# MB1256.net
KiCad netlist of a schematic drawn in Altium Designer
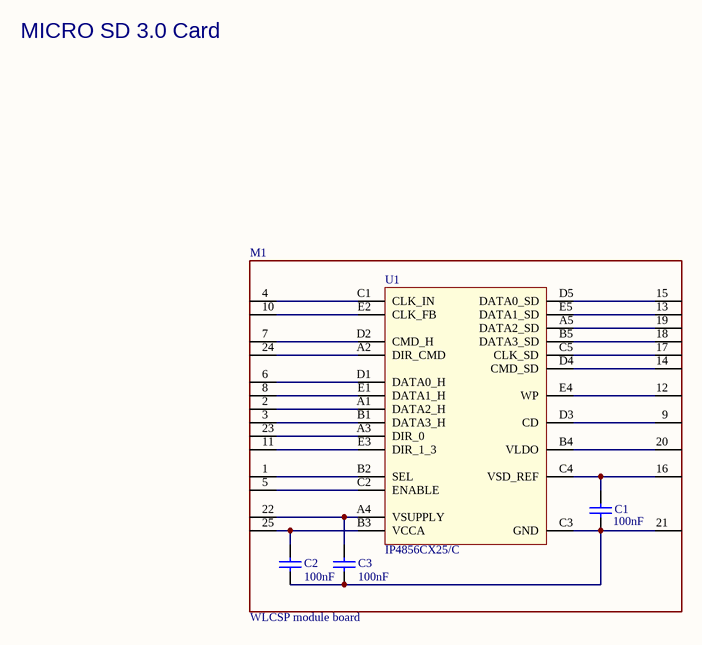
[diagram p0: MB1256.SchDoc]

(export (version "E")
  (design (tool "Eeschema 10.0.6"))
  (components
    (comp (ref "C1")
      (value "100nF")
      (footprint "0402C")
      (description "Capacitor")
      (fields (field (name "PUBLISHER") "Altium Limited"))
      (libsource (lib "Miscellaneous Devices") (part "Cap"))
    )
    (comp (ref "C2")
      (value "100nF")
      (footprint "0402C")
      (description "Capacitor")
      (fields (field (name "PUBLISHER") "Altium Limited"))
      (libsource (lib "Miscellaneous Devices") (part "Cap"))
    )
    (comp (ref "C3")
      (value "100nF")
      (footprint "0402C")
      (description "Capacitor")
      (fields (field (name "PUBLISHER") "Altium Limited"))
      (libsource (lib "Miscellaneous Devices") (part "Cap"))
    )
    (comp (ref "M1")
      (value "WLCSP module board")
      (footprint "WLCSP25_0R4_2R05X2R05_module")
      (libsource (lib "SD module board") (part "WLCSP module board"))
    )
    (comp (ref "U1")
      (value "IP4856CX25/C")
      (footprint "WLCSP25_0R4_2R05X2R05")
      (description "SDcard3.0 dual voltage level  translator")
      (libsource (lib "MB1246") (part "IP4856CX25/C"))
    )
  )
  (nets
    (net (code "1") (name "Net-(M1-CD)") (class "Default")
      (node (ref "C3") (pin "1") (pinfunction "1_1") (pintype "passive"))
      (node (ref "M1") (pin "22") (pinfunction "CD_22") (pintype "passive"))
      (node (ref "U1") (pin "A4") (pinfunction "VSUPPLY_A4") (pintype "passive"))
    )
    (net (code "2") (name "Net-(M1-CLK_FB)") (class "Default")
      (node (ref "M1") (pin "2") (pinfunction "CLK_FB_2") (pintype "passive"))
      (node (ref "U1") (pin "A1") (pinfunction "DATA2_H_A1") (pintype "passive"))
    )
    (net (code "3") (name "Net-(M1-CLK_IN)") (class "Default")
      (node (ref "M1") (pin "1") (pinfunction "CLK_IN_1") (pintype "passive"))
      (node (ref "U1") (pin "B2") (pinfunction "SEL_B2") (pintype "passive"))
    )
    (net (code "4") (name "Net-(M1-CLK_SD)") (class "Default")
      (node (ref "M1") (pin "19") (pinfunction "CLK_SD_19") (pintype "passive"))
      (node (ref "U1") (pin "A5") (pinfunction "DATA2_SD_A5") (pintype "passive"))
    )
    (net (code "5") (name "Net-(M1-CMD_H)") (class "Default")
      (node (ref "M1") (pin "3") (pinfunction "CMD_H_3") (pintype "passive"))
      (node (ref "U1") (pin "B1") (pinfunction "DATA3_H_B1") (pintype "passive"))
    )
    (net (code "6") (name "Net-(M1-CMD_SD)") (class "Default")
      (node (ref "M1") (pin "20") (pinfunction "CMD_SD_20") (pintype "passive"))
      (node (ref "U1") (pin "B4") (pinfunction "VLDO_B4") (pintype "passive"))
    )
    (net (code "7") (name "Net-(M1-DATA0_H)") (class "Default")
      (node (ref "M1") (pin "5") (pinfunction "DATA0_H_5") (pintype "passive"))
      (node (ref "U1") (pin "C2") (pinfunction "ENABLE_C2") (pintype "passive"))
    )
    (net (code "8") (name "Net-(M1-DATA0_SD)") (class "Default")
      (node (ref "M1") (pin "15") (pinfunction "DATA0_SD_15") (pintype "passive"))
      (node (ref "U1") (pin "D5") (pinfunction "DATA0_SD_D5") (pintype "passive"))
    )
    (net (code "9") (name "Net-(M1-DATA1_H)") (class "Default")
      (node (ref "M1") (pin "6") (pinfunction "DATA1_H_6") (pintype "passive"))
      (node (ref "U1") (pin "D1") (pinfunction "DATA0_H_D1") (pintype "passive"))
    )
    (net (code "10") (name "Net-(M1-DATA1_SD)") (class "Default")
      (node (ref "C1") (pin "1") (pinfunction "1_1") (pintype "passive"))
      (node (ref "M1") (pin "16") (pinfunction "DATA1_SD_16") (pintype "passive"))
      (node (ref "U1") (pin "C4") (pinfunction "VSD_REF_C4") (pintype "passive"))
    )
    (net (code "11") (name "Net-(M1-DATA2_H)") (class "Default")
      (node (ref "M1") (pin "7") (pinfunction "DATA2_H_7") (pintype "passive"))
      (node (ref "U1") (pin "D2") (pinfunction "CMD_H_D2") (pintype "passive"))
    )
    (net (code "12") (name "Net-(M1-DATA2_SD)") (class "Default")
      (node (ref "M1") (pin "17") (pinfunction "DATA2_SD_17") (pintype "passive"))
      (node (ref "U1") (pin "C5") (pinfunction "CLK_SD_C5") (pintype "passive"))
    )
    (net (code "13") (name "Net-(M1-DATA3_H)") (class "Default")
      (node (ref "M1") (pin "8") (pinfunction "DATA3_H_8") (pintype "passive"))
      (node (ref "U1") (pin "E1") (pinfunction "DATA1_H_E1") (pintype "passive"))
    )
    (net (code "14") (name "Net-(M1-DATA3_SD)") (class "Default")
      (node (ref "M1") (pin "18") (pinfunction "DATA3_SD_18") (pintype "passive"))
      (node (ref "U1") (pin "B5") (pinfunction "DATA3_SD_B5") (pintype "passive"))
    )
    (net (code "15") (name "Net-(M1-DIR_0)") (class "Default")
      (node (ref "M1") (pin "9") (pinfunction "DIR_0_9") (pintype "passive"))
      (node (ref "U1") (pin "D3") (pinfunction "CD_D3") (pintype "passive"))
    )
    (net (code "16") (name "Net-(M1-DIR_1_3)") (class "Default")
      (node (ref "M1") (pin "10") (pinfunction "DIR_1_3_10") (pintype "passive"))
      (node (ref "U1") (pin "E2") (pinfunction "CLK_FB_E2") (pintype "passive"))
    )
    (net (code "17") (name "Net-(M1-DIR_CMD)") (class "Default")
      (node (ref "M1") (pin "4") (pinfunction "DIR_CMD_4") (pintype "passive"))
      (node (ref "U1") (pin "C1") (pinfunction "CLK_IN_C1") (pintype "passive"))
    )
    (net (code "18") (name "Net-(M1-ENABLE)") (class "Default")
      (node (ref "M1") (pin "12") (pinfunction "ENABLE_12") (pintype "passive"))
      (node (ref "U1") (pin "E4") (pinfunction "WP_E4") (pintype "passive"))
    )
    (net (code "19") (name "Net-(M1-GND)") (class "Default")
      (node (ref "C2") (pin "1") (pinfunction "1_1") (pintype "passive"))
      (node (ref "M1") (pin "25") (pinfunction "GND_25") (pintype "passive"))
      (node (ref "U1") (pin "B3") (pinfunction "VCCA_B3") (pintype "passive"))
    )
    (net (code "20") (name "Net-(M1-SEL)") (class "Default")
      (node (ref "M1") (pin "11") (pinfunction "SEL_11") (pintype "passive"))
      (node (ref "U1") (pin "E3") (pinfunction "DIR_1_3_E3") (pintype "passive"))
    )
    (net (code "21") (name "Net-(M1-VCCA)") (class "Default")
      (node (ref "M1") (pin "14") (pinfunction "VCCA_14") (pintype "passive"))
      (node (ref "U1") (pin "D4") (pinfunction "CMD_SD_D4") (pintype "passive"))
    )
    (net (code "22") (name "Net-(M1-VLDO)") (class "Default")
      (node (ref "M1") (pin "23") (pinfunction "VLDO_23") (pintype "passive"))
      (node (ref "U1") (pin "A3") (pinfunction "DIR_0_A3") (pintype "passive"))
    )
    (net (code "23") (name "Net-(M1-VSD_REF)") (class "Default")
      (node (ref "M1") (pin "24") (pinfunction "VSD_REF_24") (pintype "passive"))
      (node (ref "U1") (pin "A2") (pinfunction "DIR_CMD_A2") (pintype "passive"))
    )
    (net (code "24") (name "Net-(M1-VSUPPLY)") (class "Default")
      (node (ref "M1") (pin "13") (pinfunction "VSUPPLY_13") (pintype "passive"))
      (node (ref "U1") (pin "E5") (pinfunction "DATA1_SD_E5") (pintype "passive"))
    )
    (net (code "25") (name "Net-(M1-WP)") (class "Default")
      (node (ref "C1") (pin "2") (pinfunction "2_2") (pintype "passive"))
      (node (ref "C2") (pin "2") (pinfunction "2_2") (pintype "passive"))
      (node (ref "C3") (pin "2") (pinfunction "2_2") (pintype "passive"))
      (node (ref "M1") (pin "21") (pinfunction "WP_21") (pintype "passive"))
      (node (ref "U1") (pin "C3") (pinfunction "GND_C3") (pintype "passive"))
    )
  )
)
